# Page10_BOOT_CFG.net
KiCad netlist of a schematic drawn in Altium Designer
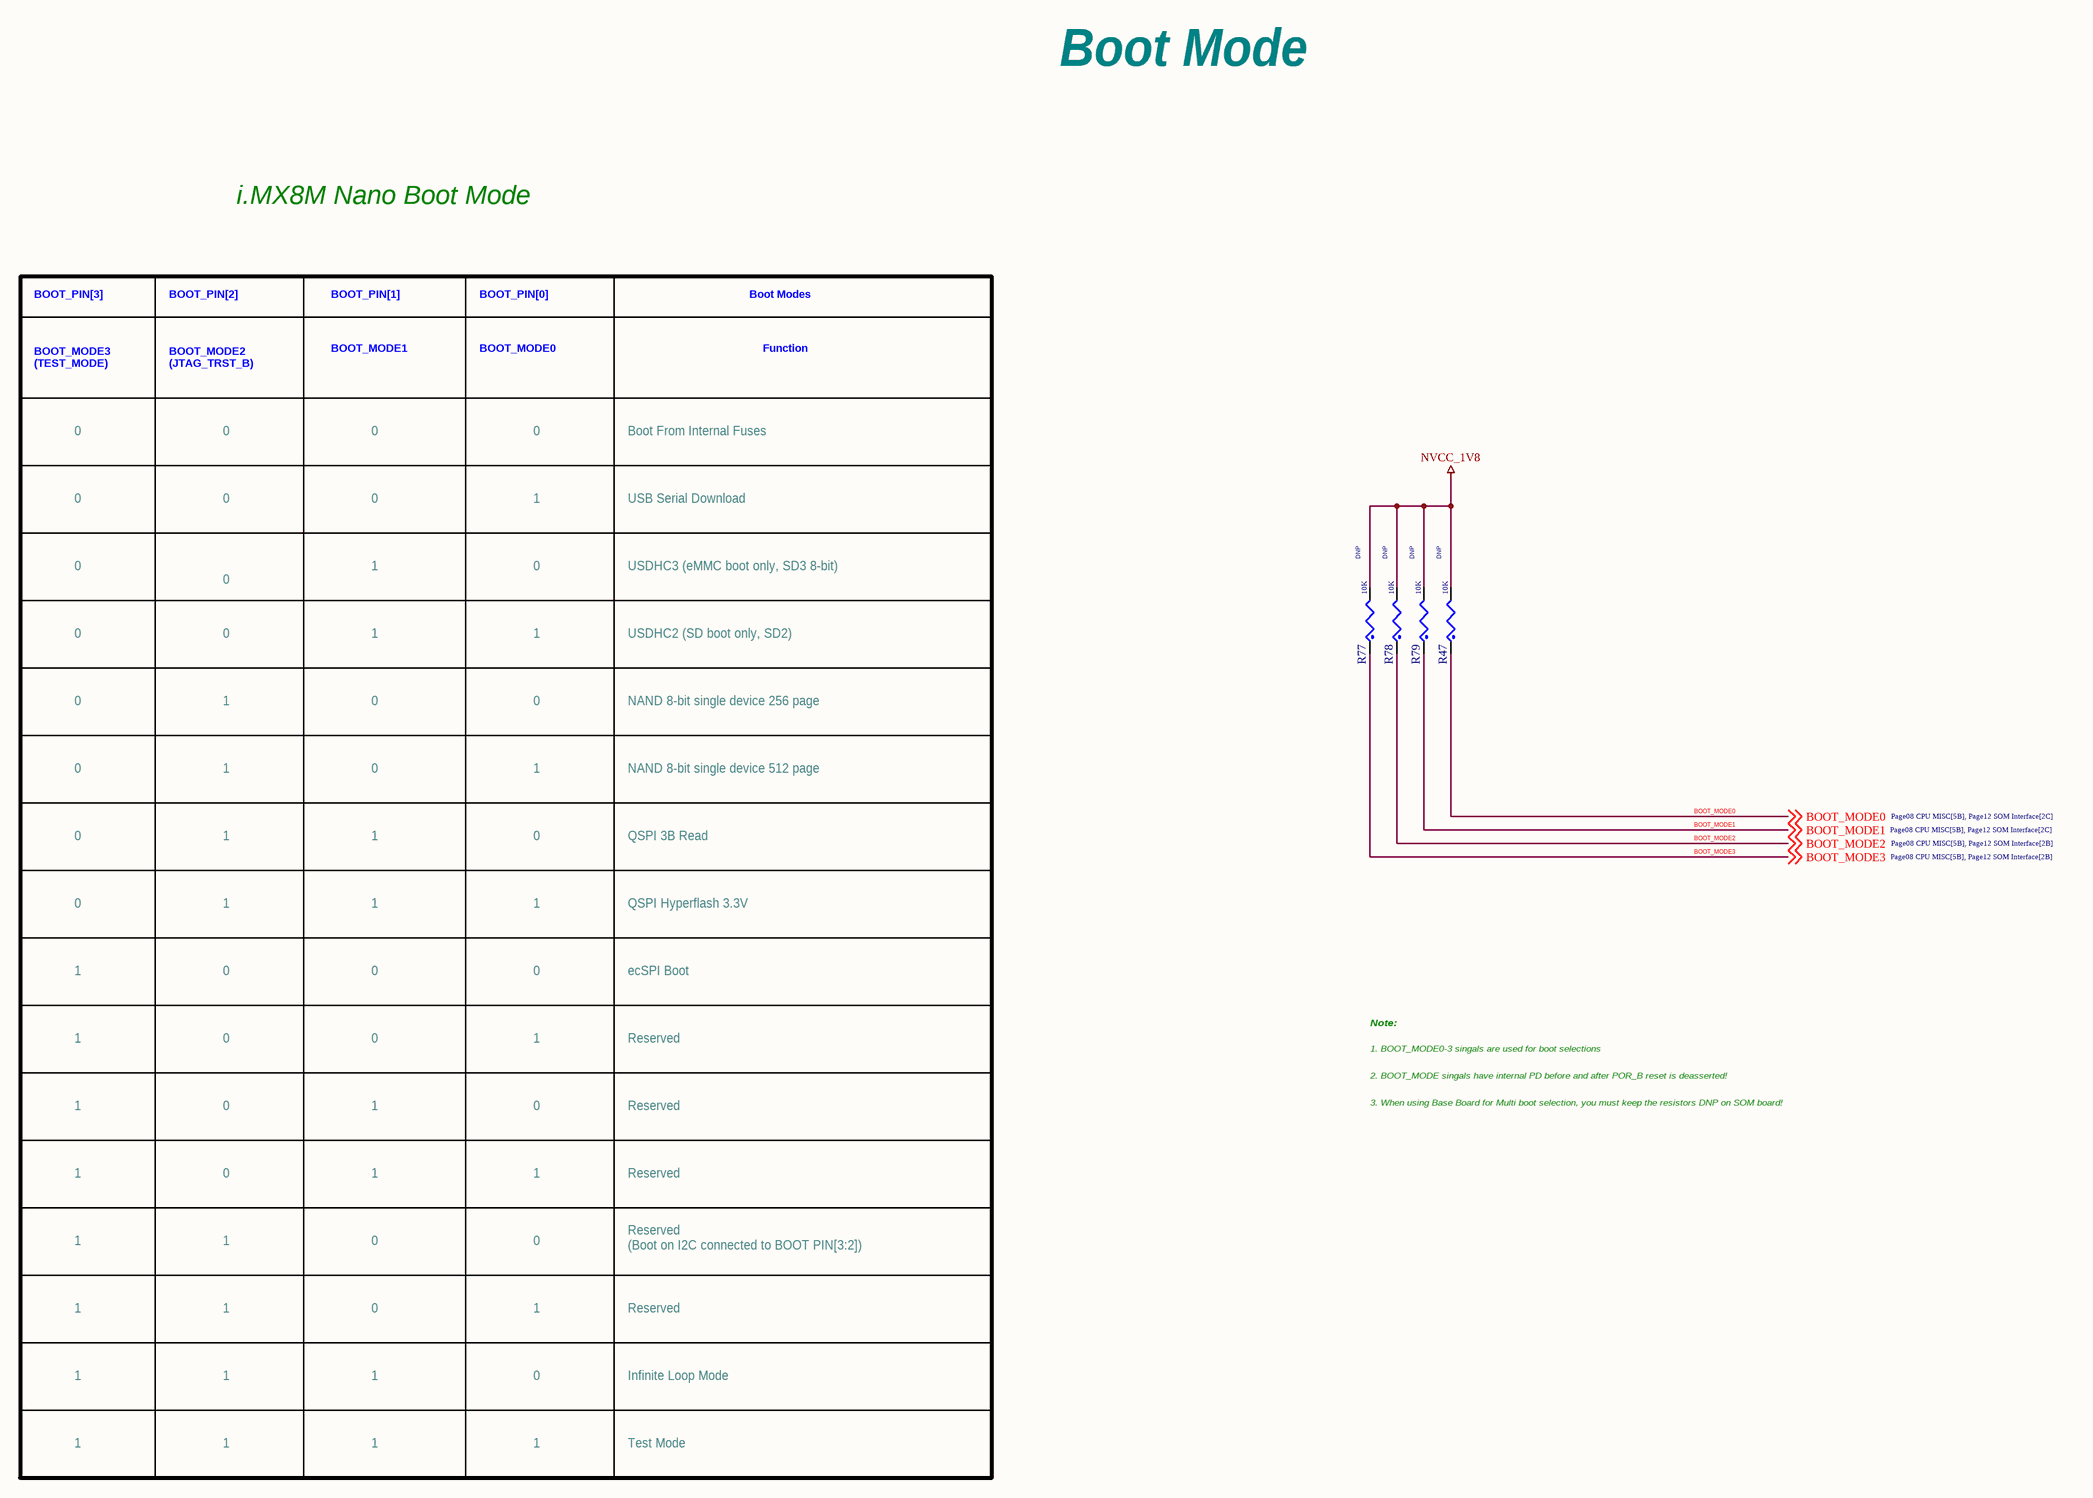
[diagram p0: Page10 BOOT_CFG.SchDoc]

(export (version "E")
  (design (tool "Eeschema 10.0.6"))
  (components
    (comp (ref "R47")
      (value "10K")
      (footprint "0402_CC_RES")
      (description "RES MF 10K 1/16W 5% 0402")
      (fields (field (name "ASSY_OPT") "DNP") (field (name "TOLERANCE") "5%"))
      (libsource (lib "*") (part "RES"))
    )
    (comp (ref "R77")
      (value "10K")
      (footprint "0402_CC_RES")
      (description "RES MF 10K 1/16W 5% 0402")
      (fields (field (name "ASSY_OPT") "DNP") (field (name "TOLERANCE") "5%"))
      (libsource (lib "*") (part "RES"))
    )
    (comp (ref "R78")
      (value "10K")
      (footprint "0402_CC_RES")
      (description "RES MF 10K 1/16W 5% 0402")
      (fields (field (name "ASSY_OPT") "DNP") (field (name "TOLERANCE") "5%"))
      (libsource (lib "*") (part "RES"))
    )
    (comp (ref "R79")
      (value "10K")
      (footprint "0402_CC_RES")
      (description "RES MF 10K 1/16W 5% 0402")
      (fields (field (name "ASSY_OPT") "DNP") (field (name "TOLERANCE") "5%"))
      (libsource (lib "*") (part "RES"))
    )
  )
  (nets
    (net (code "1") (name "BOOT_MODE0") (class "Default")
      (node (ref "R47") (pin "1") (pinfunction "1_1") (pintype "passive"))
    )
    (net (code "2") (name "BOOT_MODE1") (class "Default")
      (node (ref "R79") (pin "1") (pinfunction "1_1") (pintype "passive"))
    )
    (net (code "3") (name "BOOT_MODE2") (class "Default")
      (node (ref "R78") (pin "1") (pinfunction "1_1") (pintype "passive"))
    )
    (net (code "4") (name "BOOT_MODE3") (class "Default")
      (node (ref "R77") (pin "1") (pinfunction "1_1") (pintype "passive"))
    )
    (net (code "5") (name "NVCC_1V8") (class "Default")
      (node (ref "R47") (pin "2") (pinfunction "2_2") (pintype "passive"))
      (node (ref "R77") (pin "2") (pinfunction "2_2") (pintype "passive"))
      (node (ref "R78") (pin "2") (pinfunction "2_2") (pintype "passive"))
      (node (ref "R79") (pin "2") (pinfunction "2_2") (pintype "passive"))
    )
  )
)
